# 05-SX1276.net
KiCad netlist of a schematic drawn in Altium Designer
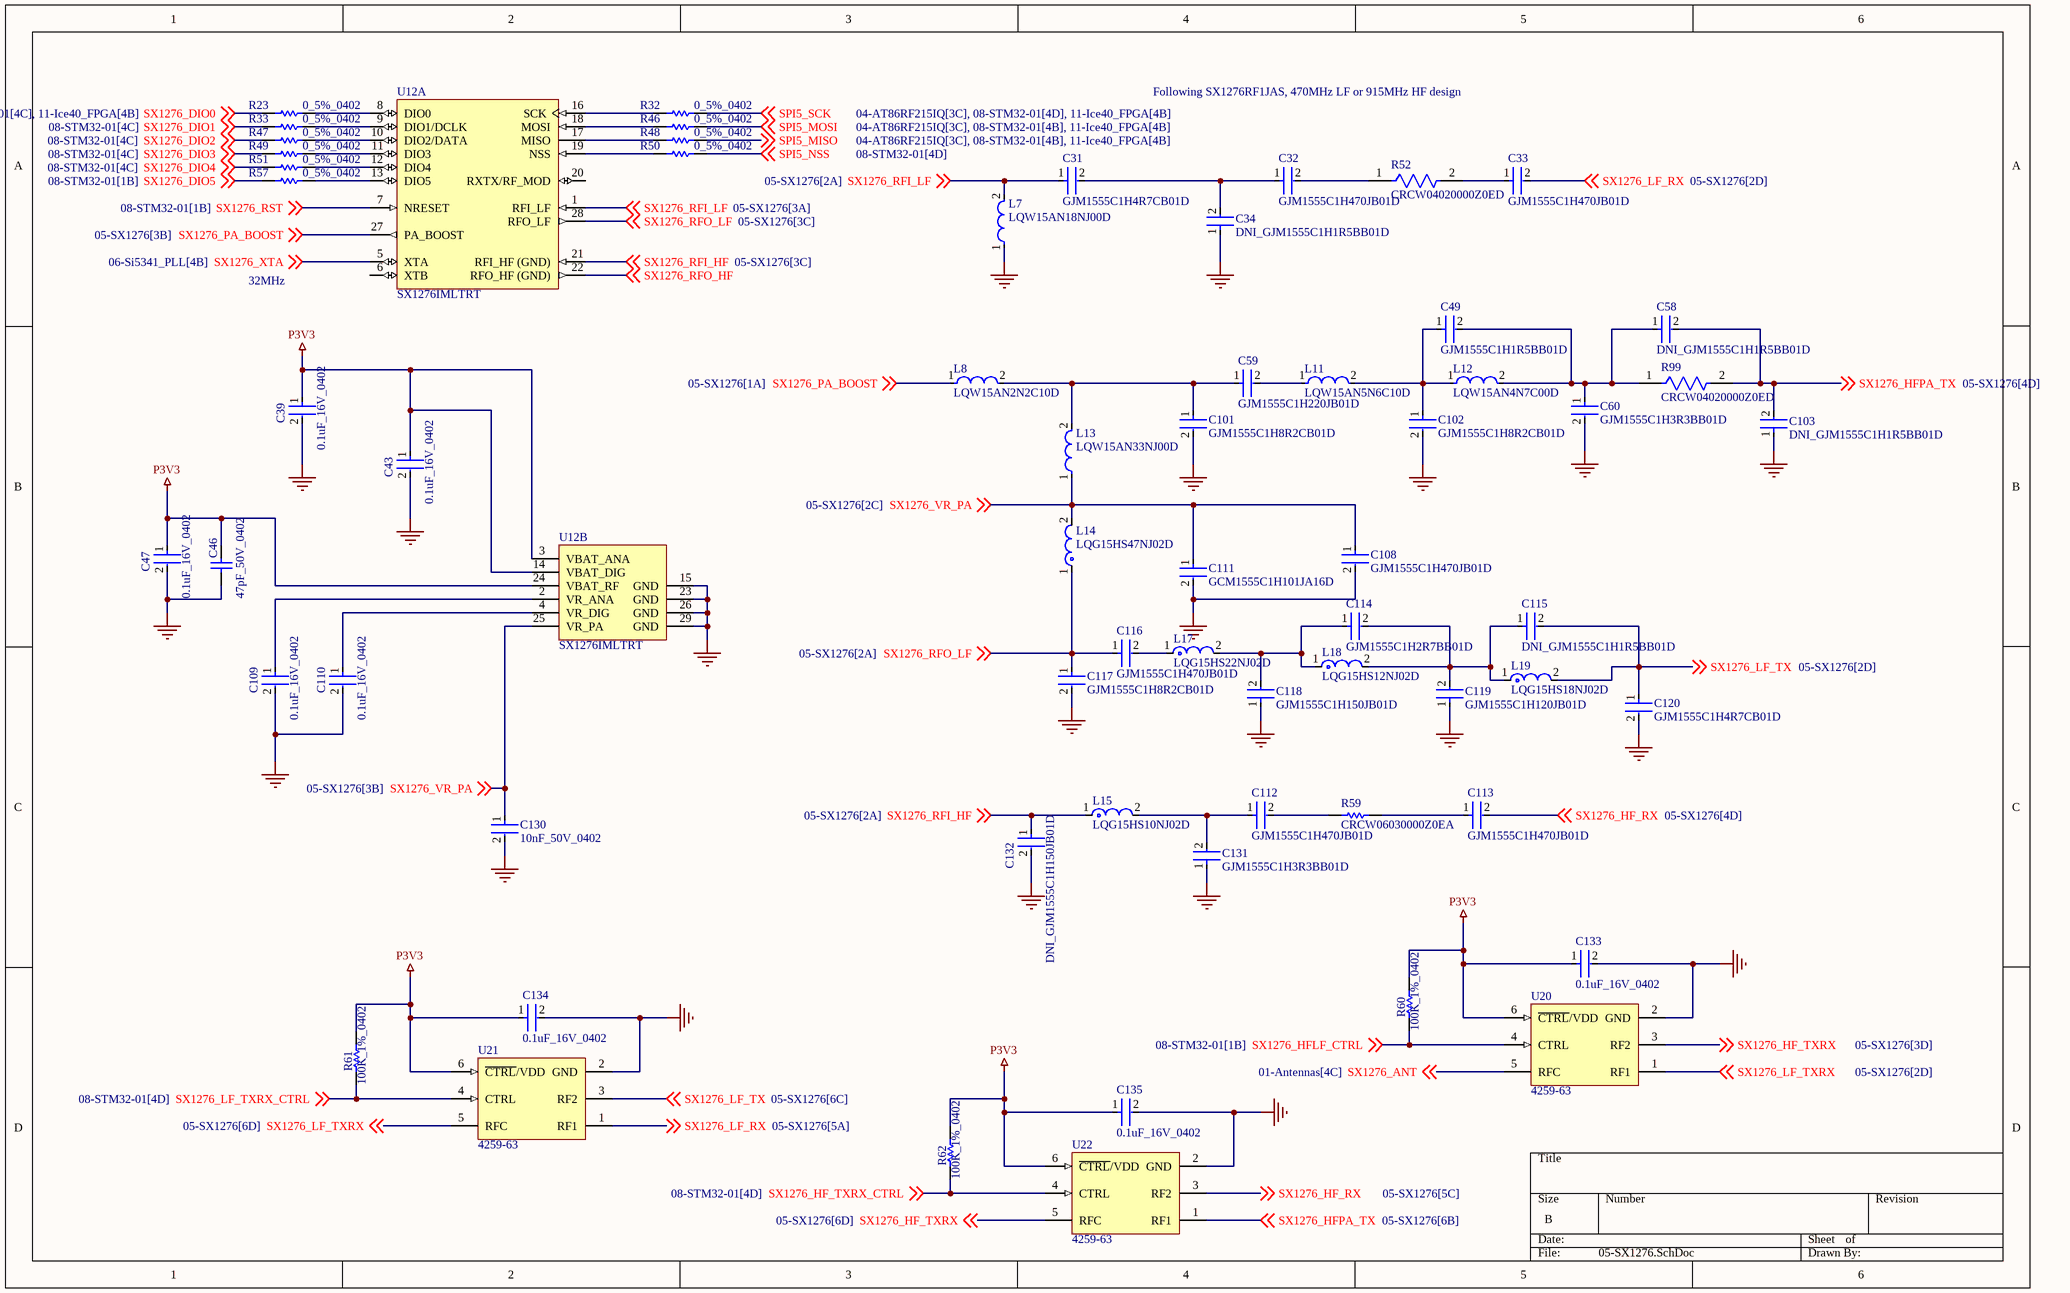
[diagram p0: 05-SX1276.SchDoc]

(export (version "E")
  (design (tool "Eeschema 10.0.6"))
  (components
    (comp (ref "C31")
      (value "GJM1555C1H4R7CB01D")
      (footprint "FP-GJM155-0_05-IPC_B")
      (description "Multi-Layer Ceramic Capacitor 4.7pF C0G  ±0.25pF 0402 Paper T/R")
      (fields (field (name "VOLTAGE") "50V"))
      (libsource (lib "Altium Content Vault") (part "02cd4be3c70576c341d710602a673aa"))
    )
    (comp (ref "C32")
      (value "GJM1555C1H470JB01D")
      (footprint "FP-GJM155-0_05-MFG")
      (description "Multi-Layer Ceramic Capacitor 47pF C0G  ±5% 0402 Paper T/R")
      (fields (field (name "TOLERANCE") "5%"))
      (libsource (lib "Altium Content Vault") (part "02cd4be3c70576c341d710602a673aa"))
    )
    (comp (ref "C33")
      (value "GJM1555C1H470JB01D")
      (footprint "FP-GJM155-0_05-MFG")
      (description "Multi-Layer Ceramic Capacitor 47pF C0G  ±5% 0402 Paper T/R")
      (fields (field (name "TOLERANCE") "5%"))
      (libsource (lib "Altium Content Vault") (part "02cd4be3c70576c341d710602a673aa"))
    )
    (comp (ref "C34")
      (value "DNI_GJM1555C1H1R5BB01D")
      (footprint "FP-GJM155-0_05-IPC_C")
      (description "Multi-Layer Ceramic Capacitor 1.5pF C0G  ±0.1pF 0402 Paper T/R")
      (fields (field (name "VOLTAGE") "50V"))
      (libsource (lib "Altium Content Vault") (part "02cd4be3c70576c341d710602a673aa"))
    )
    (comp (ref "C39")
      (value "0.1uF_16V_0402")
      (footprint "FP-C0402-BB-MFG")
      (description "CAP CER 0.1UF 16V 5% X7R 0402")
      (fields
        (field (name "MANUFACTURER") "Kemet")
        (field (name "MANUFACTURER PART NUMBER") "C0402C104J4RACTU")
      )
      (libsource (lib "Altium Content Vault") (part "b4654b650e69147ec39a6b967a45e02"))
    )
    (comp (ref "C43")
      (value "0.1uF_16V_0402")
      (footprint "FP-C0402-BB-MFG")
      (description "CAP CER 0.1UF 16V 5% X7R 0402")
      (fields
        (field (name "MANUFACTURER") "Kemet")
        (field (name "MANUFACTURER PART NUMBER") "C0402C104J4RACTU")
      )
      (libsource (lib "Altium Content Vault") (part "b4654b650e69147ec39a6b967a45e02"))
    )
    (comp (ref "C46")
      (value "47pF_50V_0402")
      (footprint "CAPC1005X55X25LL05T10")
      (fields (field (name "PART NUMBER") "GRM1555C1H470JA01D") (field (name "MANUFACTURER") "Murata"))
      (libsource (lib "Altium Content Vault") (part "CAP"))
    )
    (comp (ref "C47")
      (value "0.1uF_16V_0402")
      (footprint "FP-C0402-BB-MFG")
      (description "CAP CER 0.1UF 16V 5% X7R 0402")
      (fields
        (field (name "MANUFACTURER") "Kemet")
        (field (name "MANUFACTURER PART NUMBER") "C0402C104J4RACTU")
      )
      (libsource (lib "Altium Content Vault") (part "b4654b650e69147ec39a6b967a45e02"))
    )
    (comp (ref "C49")
      (value "GJM1555C1H1R5BB01D")
      (footprint "FP-GJM155-0_05-IPC_C")
      (description "Multi-Layer Ceramic Capacitor 1.5pF C0G  ±0.1pF 0402 Paper T/R")
      (fields (field (name "VOLTAGE") "50V"))
      (libsource (lib "Altium Content Vault") (part "02cd4be3c70576c341d710602a673aa"))
    )
    (comp (ref "C58")
      (value "DNI_GJM1555C1H1R5BB01D")
      (footprint "FP-GJM155-0_05-IPC_C")
      (description "Multi-Layer Ceramic Capacitor 1.5pF C0G  ±0.1pF 0402 Paper T/R")
      (fields (field (name "VOLTAGE") "50V"))
      (libsource (lib "Altium Content Vault") (part "02cd4be3c70576c341d710602a673aa"))
    )
    (comp (ref "C59")
      (value "GJM1555C1H220JB01D")
      (footprint "FP-GJM155-0_05-IPC_C")
      (description "Multi-Layer Ceramic Capacitor 22pF C0G  ±5% 0402 Paper T/R")
      (fields (field (name "TOLERANCE") "5%"))
      (libsource (lib "Altium Content Vault") (part "02cd4be3c70576c341d710602a673aa"))
    )
    (comp (ref "C60")
      (value "GJM1555C1H3R3BB01D")
      (footprint "FP-GJM155-0_05-IPC_C")
      (description "Multi-Layer Ceramic Capacitor 3.3pF C0G  ±0.1pF 0402 Paper T/R")
      (fields (field (name "VOLTAGE") "50V"))
      (libsource (lib "Altium Content Vault") (part "02cd4be3c70576c341d710602a673aa"))
    )
    (comp (ref "C101")
      (value "GJM1555C1H8R2CB01D")
      (footprint "FP-GJM155-0_05-IPC_C")
      (description "Multi-Layer Ceramic Capacitor 8.2pF C0G  ±0.25pF 0402 Paper T/R")
      (fields (field (name "VOLTAGE") "50V"))
      (libsource (lib "Altium Content Vault") (part "02cd4be3c70576c341d710602a673aa"))
    )
    (comp (ref "C102")
      (value "GJM1555C1H8R2CB01D")
      (footprint "FP-GJM155-0_05-IPC_C")
      (description "Multi-Layer Ceramic Capacitor 8.2pF C0G  ±0.25pF 0402 Paper T/R")
      (fields (field (name "VOLTAGE") "50V"))
      (libsource (lib "Altium Content Vault") (part "02cd4be3c70576c341d710602a673aa"))
    )
    (comp (ref "C103")
      (value "DNI_GJM1555C1H1R5BB01D")
      (footprint "FP-GJM155-0_05-IPC_C")
      (description "Multi-Layer Ceramic Capacitor 1.5pF C0G  ±0.1pF 0402 Paper T/R")
      (fields (field (name "VOLTAGE") "50V"))
      (libsource (lib "Altium Content Vault") (part "02cd4be3c70576c341d710602a673aa"))
    )
    (comp (ref "C108")
      (value "GJM1555C1H470JB01D")
      (footprint "FP-GJM155-0_05-MFG")
      (description "Multi-Layer Ceramic Capacitor 47pF C0G  ±5% 0402 Paper T/R")
      (fields (field (name "TOLERANCE") "5%"))
      (libsource (lib "Altium Content Vault") (part "02cd4be3c70576c341d710602a673aa"))
    )
    (comp (ref "C109")
      (value "0.1uF_16V_0402")
      (footprint "FP-C0402-BB-MFG")
      (description "CAP CER 0.1UF 16V 5% X7R 0402")
      (fields
        (field (name "MANUFACTURER") "Kemet")
        (field (name "MANUFACTURER PART NUMBER") "C0402C104J4RACTU")
      )
      (libsource (lib "Altium Content Vault") (part "b4654b650e69147ec39a6b967a45e02"))
    )
    (comp (ref "C110")
      (value "0.1uF_16V_0402")
      (footprint "FP-C0402-BB-MFG")
      (description "CAP CER 0.1UF 16V 5% X7R 0402")
      (fields
        (field (name "MANUFACTURER") "Kemet")
        (field (name "MANUFACTURER PART NUMBER") "C0402C104J4RACTU")
      )
      (libsource (lib "Altium Content Vault") (part "b4654b650e69147ec39a6b967a45e02"))
    )
    (comp (ref "C111")
      (value "GCM1555C1H101JA16D")
      (footprint "FP-GCM155-0_05-IPC_C")
      (description "Ceramic Capacitor for Automotive 100pF ±5% 50VDC C0G 0402 Paper T/R")
      (fields (field (name "VOLTAGE") "50V") (field (name "TOLERANCE") "5%"))
      (libsource (lib "Altium Content Vault") (part "02cd4be3c70576c341d710602a673aa"))
    )
    (comp (ref "C112")
      (value "GJM1555C1H470JB01D")
      (footprint "FP-GJM155-0_05-MFG")
      (description "Multi-Layer Ceramic Capacitor 47pF C0G  ±5% 0402 Paper T/R")
      (fields (field (name "TOLERANCE") "5%"))
      (libsource (lib "Altium Content Vault") (part "02cd4be3c70576c341d710602a673aa"))
    )
    (comp (ref "C113")
      (value "GJM1555C1H470JB01D")
      (footprint "FP-GJM155-0_05-MFG")
      (description "Multi-Layer Ceramic Capacitor 47pF C0G  ±5% 0402 Paper T/R")
      (fields (field (name "TOLERANCE") "5%"))
      (libsource (lib "Altium Content Vault") (part "02cd4be3c70576c341d710602a673aa"))
    )
    (comp (ref "C114")
      (value "GJM1555C1H2R7BB01D")
      (footprint "FP-GJM155-0_05-IPC_A")
      (description "Multi-Layer Ceramic Capacitor 2.7pF C0G  ±0.1pF 0402 Paper T/R")
      (fields (field (name "VOLTAGE") "50V"))
      (libsource (lib "Altium Content Vault") (part "02cd4be3c70576c341d710602a673aa"))
    )
    (comp (ref "C115")
      (value "DNI_GJM1555C1H1R5BB01D")
      (footprint "FP-GJM155-0_05-IPC_C")
      (description "Multi-Layer Ceramic Capacitor 1.5pF C0G  ±0.1pF 0402 Paper T/R")
      (fields (field (name "VOLTAGE") "50V"))
      (libsource (lib "Altium Content Vault") (part "02cd4be3c70576c341d710602a673aa"))
    )
    (comp (ref "C116")
      (value "GJM1555C1H470JB01D")
      (footprint "FP-GJM155-0_05-MFG")
      (description "Multi-Layer Ceramic Capacitor 47pF C0G  ±5% 0402 Paper T/R")
      (fields (field (name "TOLERANCE") "5%"))
      (libsource (lib "Altium Content Vault") (part "02cd4be3c70576c341d710602a673aa"))
    )
    (comp (ref "C117")
      (value "GJM1555C1H8R2CB01D")
      (footprint "FP-GJM155-0_05-IPC_C")
      (description "Multi-Layer Ceramic Capacitor 8.2pF C0G  ±0.25pF 0402 Paper T/R")
      (fields (field (name "VOLTAGE") "50V"))
      (libsource (lib "Altium Content Vault") (part "02cd4be3c70576c341d710602a673aa"))
    )
    (comp (ref "C118")
      (value "GJM1555C1H150JB01D")
      (footprint "FP-GJM155-0_05-IPC_A")
      (description "Multi-Layer Ceramic Capacitor 15pF C0G  ±5% 0402 Paper T/R")
      (fields (field (name "TOLERANCE") "5%") (field (name "VOLTAGE") "50V"))
      (libsource (lib "Altium Content Vault") (part "02cd4be3c70576c341d710602a673aa"))
    )
    (comp (ref "C119")
      (value "GJM1555C1H120JB01D")
      (footprint "FP-GJM155-0_05-IPC_A")
      (description "Multi-Layer Ceramic Capacitor 12pF C0G  ±5% 0402 Paper T/R")
      (fields (field (name "TOLERANCE") "5%") (field (name "VOLTAGE") "50V"))
      (libsource (lib "Altium Content Vault") (part "02cd4be3c70576c341d710602a673aa"))
    )
    (comp (ref "C120")
      (value "GJM1555C1H4R7CB01D")
      (footprint "FP-GJM155-0_05-IPC_B")
      (description "Multi-Layer Ceramic Capacitor 4.7pF C0G  ±0.25pF 0402 Paper T/R")
      (fields (field (name "VOLTAGE") "50V"))
      (libsource (lib "Altium Content Vault") (part "02cd4be3c70576c341d710602a673aa"))
    )
    (comp (ref "C130")
      (value "10nF_50V_0402")
      (footprint "FP-CL165-IPC_C")
      (description "Cap Ceramic 10nF 50V X7R ±10% SMD 0402 +125°C Paper T/R")
      (fields (field (name "VOLTAGE") "50V") (field (name "TOLERANCE") "10%"))
      (libsource (lib "Altium Content Vault") (part "b4654b650e69147ec39a6b967a45e02"))
    )
    (comp (ref "C131")
      (value "GJM1555C1H3R3BB01D")
      (footprint "FP-GJM155-0_05-IPC_C")
      (description "Multi-Layer Ceramic Capacitor 3.3pF C0G  ±0.1pF 0402 Paper T/R")
      (fields (field (name "VOLTAGE") "50V"))
      (libsource (lib "Altium Content Vault") (part "02cd4be3c70576c341d710602a673aa"))
    )
    (comp (ref "C132")
      (value "DNI_GJM1555C1H150JB01D")
      (footprint "FP-GJM155-0_05-IPC_A")
      (description "Multi-Layer Ceramic Capacitor 15pF C0G  ±5% 0402 Paper T/R")
      (fields (field (name "TOLERANCE") "5%") (field (name "VOLTAGE") "50V"))
      (libsource (lib "Altium Content Vault") (part "02cd4be3c70576c341d710602a673aa"))
    )
    (comp (ref "C133")
      (value "0.1uF_16V_0402")
      (footprint "FP-C0402-BB-MFG")
      (description "CAP CER 0.1UF 16V 5% X7R 0402")
      (fields
        (field (name "MANUFACTURER") "Kemet")
        (field (name "MANUFACTURER PART NUMBER") "C0402C104J4RACTU")
      )
      (libsource (lib "Altium Content Vault") (part "b4654b650e69147ec39a6b967a45e02"))
    )
    (comp (ref "C134")
      (value "0.1uF_16V_0402")
      (footprint "FP-C0402-BB-MFG")
      (description "CAP CER 0.1UF 16V 5% X7R 0402")
      (fields
        (field (name "MANUFACTURER") "Kemet")
        (field (name "MANUFACTURER PART NUMBER") "C0402C104J4RACTU")
      )
      (libsource (lib "Altium Content Vault") (part "b4654b650e69147ec39a6b967a45e02"))
    )
    (comp (ref "C135")
      (value "0.1uF_16V_0402")
      (footprint "FP-C0402-BB-MFG")
      (description "CAP CER 0.1UF 16V 5% X7R 0402")
      (fields
        (field (name "MANUFACTURER") "Kemet")
        (field (name "MANUFACTURER PART NUMBER") "C0402C104J4RACTU")
      )
      (libsource (lib "Altium Content Vault") (part "b4654b650e69147ec39a6b967a45e02"))
    )
    (comp (ref "L7")
      (value "LQW15AN18NJ00D")
      (footprint "FP-LQW15AN_00-W0_6-0_1-MFG")
      (description "Wire Wound RF Inductor 18nH ±5% 370mA 0.27Ω 0402 (1005)")
      (fields (field (name "TOLERANCE") "5%"))
      (libsource (lib "Altium Content Vault") (part "725321dda6339637d4d059423bc1c3c"))
    )
    (comp (ref "L8")
      (value "LQW15AN2N2C10D")
      (footprint "FP-LQW15AN_00-W0_6-0_1-MFG")
      (description "Wire Wound RF Inductor 2.2nH ±0.2nH 1000mA 0.027Ω 0402 (1005)")
      (libsource (lib "Altium Content Vault") (part "725321dda6339637d4d059423bc1c3c"))
    )
    (comp (ref "L11")
      (value "LQW15AN5N6C10D")
      (footprint "FP-LQW15AN_00-W0_6-0_1-MFG")
      (description "Wire Wound RF Inductor 5.6nH ±0.2nH 800mA 0.051Ω 0402 (1005)")
      (libsource (lib "Altium Content Vault") (part "725321dda6339637d4d059423bc1c3c"))
    )
    (comp (ref "L12")
      (value "LQW15AN4N7C00D")
      (footprint "FP-LQW15AN_00-W0_6-0_1-MFG")
      (description "Wire Wound RF Inductor 4.7nH ±0.2nH 750mA 0.07Ω 0402 (1005)")
      (libsource (lib "Altium Content Vault") (part "725321dda6339637d4d059423bc1c3c"))
    )
    (comp (ref "L13")
      (value "LQW15AN33NJ00D")
      (footprint "FP-LQW15AN_00-W0_5-0_1-MFG")
      (description "Wire Wound RF Inductor 33nH ±5% 260mA 0.63Ω 0402 (1005)")
      (fields (field (name "TOLERANCE") "5%"))
      (libsource (lib "Altium Content Vault") (part "725321dda6339637d4d059423bc1c3c"))
    )
    (comp (ref "L14")
      (value "LQG15HS47NJ02D")
      (footprint "FP-LQG15HH_02-IPC_B")
      (description "Multilayer type RF Inductor 47nH ±5% 0.72Ω 300mA 0402")
      (fields (field (name "TOLERANCE") "5%"))
      (libsource (lib "Altium Content Vault") (part "4cc4b267dca4c8e51f7102f422741d8"))
    )
    (comp (ref "L15")
      (value "LQG15HS10NJ02D")
      (footprint "FP-LQG15HH_02-IPC_A")
      (description "Multilayer type RF Inductor 10nH ±5% 0.26Ω 500mA 0402")
      (fields (field (name "TOLERANCE") "5%"))
      (libsource (lib "Altium Content Vault") (part "4cc4b267dca4c8e51f7102f422741d8"))
    )
    (comp (ref "L17")
      (value "LQG15HS22NJ02D")
      (footprint "FP-LQG15HH_02-MFG")
      (description "Multilayer type RF Inductor 22nH ±5% 0.42Ω 350mA 0402")
      (fields (field (name "TOLERANCE") "5%"))
      (libsource (lib "Altium Content Vault") (part "4cc4b267dca4c8e51f7102f422741d8"))
    )
    (comp (ref "L18")
      (value "LQG15HS12NJ02D")
      (footprint "FP-LQG15HH_02-IPC_A")
      (description "Multilayer type RF Inductor 12nH ±5% 0.28Ω 500mA 0402")
      (fields (field (name "TOLERANCE") "5%"))
      (libsource (lib "Altium Content Vault") (part "4cc4b267dca4c8e51f7102f422741d8"))
    )
    (comp (ref "L19")
      (value "LQG15HS18NJ02D")
      (footprint "FP-LQG15HH_02-MFG")
      (description "Multilayer type RF Inductor 18nH ±5% 0.36Ω 400mA 0402")
      (fields (field (name "TOLERANCE") "5%"))
      (libsource (lib "Altium Content Vault") (part "4cc4b267dca4c8e51f7102f422741d8"))
    )
    (comp (ref "R23")
      (value "0_5%_0402")
      (footprint "RESC1005X40X25NL05T10")
      (fields (field (name "MANUFACTURER") "Panasonic") (field (name "PART NUMBER") "ERJ-U020R00X"))
      (libsource (lib "Altium Content Vault") (part "RES"))
    )
    (comp (ref "R32")
      (value "0_5%_0402")
      (footprint "RESC1005X40X25NL05T10")
      (fields (field (name "MANUFACTURER") "Panasonic") (field (name "PART NUMBER") "ERJ-U020R00X"))
      (libsource (lib "Altium Content Vault") (part "RES"))
    )
    (comp (ref "R33")
      (value "0_5%_0402")
      (footprint "RESC1005X40X25NL05T10")
      (fields (field (name "MANUFACTURER") "Panasonic") (field (name "PART NUMBER") "ERJ-U020R00X"))
      (libsource (lib "Altium Content Vault") (part "RES"))
    )
    (comp (ref "R46")
      (value "0_5%_0402")
      (footprint "RESC1005X40X25NL05T10")
      (fields (field (name "MANUFACTURER") "Panasonic") (field (name "PART NUMBER") "ERJ-U020R00X"))
      (libsource (lib "Altium Content Vault") (part "RES"))
    )
    (comp (ref "R47")
      (value "0_5%_0402")
      (footprint "RESC1005X40X25NL05T10")
      (fields (field (name "MANUFACTURER") "Panasonic") (field (name "PART NUMBER") "ERJ-U020R00X"))
      (libsource (lib "Altium Content Vault") (part "RES"))
    )
    (comp (ref "R48")
      (value "0_5%_0402")
      (footprint "RESC1005X40X25NL05T10")
      (fields (field (name "MANUFACTURER") "Panasonic") (field (name "PART NUMBER") "ERJ-U020R00X"))
      (libsource (lib "Altium Content Vault") (part "RES"))
    )
    (comp (ref "R49")
      (value "0_5%_0402")
      (footprint "RESC1005X40X25NL05T10")
      (fields (field (name "MANUFACTURER") "Panasonic") (field (name "PART NUMBER") "ERJ-U020R00X"))
      (libsource (lib "Altium Content Vault") (part "RES"))
    )
    (comp (ref "R50")
      (value "0_5%_0402")
      (footprint "RESC1005X40X25NL05T10")
      (fields (field (name "MANUFACTURER") "Panasonic") (field (name "PART NUMBER") "ERJ-U020R00X"))
      (libsource (lib "Altium Content Vault") (part "RES"))
    )
    (comp (ref "R51")
      (value "0_5%_0402")
      (footprint "RESC1005X40X25NL05T10")
      (fields (field (name "MANUFACTURER") "Panasonic") (field (name "PART NUMBER") "ERJ-U020R00X"))
      (libsource (lib "Altium Content Vault") (part "RES"))
    )
    (comp (ref "R52")
      (value "CRCW04020000Z0ED")
      (footprint "FP-CRCW0402-e3-IPC_C")
      (description "RES Thick Film, 0Ω, 0.063W, 0402")
      (fields (field (name "TOLERANCE") "5%"))
      (libsource (lib "Altium Content Vault") (part "1029c3af85768c4190bb7ad29bc67b5"))
    )
    (comp (ref "R57")
      (value "0_5%_0402")
      (footprint "RESC1005X40X25NL05T10")
      (fields (field (name "MANUFACTURER") "Panasonic") (field (name "PART NUMBER") "ERJ-U020R00X"))
      (libsource (lib "Altium Content Vault") (part "RES"))
    )
    (comp (ref "R59")
      (value "CRCW06030000Z0EA")
      (footprint "RESC1609X50X30NL8T20")
      (description "Chip Resistor, 0 Ohm, Jumper, 100 mW, -55 to 155 degC, 0603 (1608 Metric), RoHS, Tape and Reel")
      (fields (field (name "MANUFACTURER") "Vishay Semiconductor"))
      (libsource (lib "Altium Content Vault") (part "RES-2"))
    )
    (comp (ref "R60")
      (value "100K_1%_0402")
      (footprint "RESC1005X40X25ML05T10")
      (fields (field (name "MANUFACTURER") "Yageo") (field (name "PART NUMBER") "RC0402FR-13100KL"))
      (libsource (lib "Altium Content Vault") (part "RES"))
    )
    (comp (ref "R61")
      (value "100K_1%_0402")
      (footprint "RESC1005X40X25ML05T10")
      (fields (field (name "MANUFACTURER") "Yageo") (field (name "PART NUMBER") "RC0402FR-13100KL"))
      (libsource (lib "Altium Content Vault") (part "RES"))
    )
    (comp (ref "R62")
      (value "100K_1%_0402")
      (footprint "RESC1005X40X25ML05T10")
      (fields (field (name "MANUFACTURER") "Yageo") (field (name "PART NUMBER") "RC0402FR-13100KL"))
      (libsource (lib "Altium Content Vault") (part "RES"))
    )
    (comp (ref "R99")
      (value "CRCW04020000Z0ED")
      (footprint "FP-CRCW0402-e3-IPC_C")
      (description "RES Thick Film, 0Ω, 0.063W, 0402")
      (fields (field (name "TOLERANCE") "5%"))
      (libsource (lib "Altium Content Vault") (part "1029c3af85768c4190bb7ad29bc67b5"))
    )
    (comp (ref "U12")
      (value "SX1276IMLTRT")
      (footprint "SMTC-QFN-28_V")
      (description "Low Power Long Range Transceiver, 137 to 1020 MHz, -40 to 85 degC, 28-Pin QFN, RoHS, Tape and Reel")
      (fields (field (name "MANUFACTURER") "Semtech"))
      (libsource (lib "Altium Content Vault") (part "SMTC-SX127X-QFN-28"))
    )
    (comp (ref "U20")
      (value "4259-63")
      (footprint "PERE-SC-70-6_M")
      (description "IC RF Switch SPDT, 50 Ohm, 6-Pin SC70, RoHS, Tape and Reel")
      (fields (field (name "MANUFACTURER") "Peregrine Semiconductor"))
      (libsource (lib "Altium Content Vault") (part "PERE-PE4259-6"))
    )
    (comp (ref "U21")
      (value "4259-63")
      (footprint "PERE-SC-70-6_M")
      (description "IC RF Switch SPDT, 50 Ohm, 6-Pin SC70, RoHS, Tape and Reel")
      (fields (field (name "MANUFACTURER") "Peregrine Semiconductor"))
      (libsource (lib "Altium Content Vault") (part "PERE-PE4259-6"))
    )
    (comp (ref "U22")
      (value "4259-63")
      (footprint "PERE-SC-70-6_M")
      (description "IC RF Switch SPDT, 50 Ohm, 6-Pin SC70, RoHS, Tape and Reel")
      (fields (field (name "MANUFACTURER") "Peregrine Semiconductor"))
      (libsource (lib "Altium Content Vault") (part "PERE-PE4259-6"))
    )
  )
  (nets
    (net (code "1") (name "GND") (class "Default")
      (node (ref "C101") (pin "2") (pinfunction "2_2") (pintype "passive"))
      (node (ref "C102") (pin "2") (pinfunction "2_2") (pintype "passive"))
      (node (ref "C103") (pin "1") (pinfunction "1_1") (pintype "passive"))
      (node (ref "C108") (pin "2") (pinfunction "2_2") (pintype "passive"))
      (node (ref "C109") (pin "2") (pinfunction "2_2") (pintype "passive"))
      (node (ref "C110") (pin "2") (pinfunction "2_2") (pintype "passive"))
      (node (ref "C111") (pin "2") (pinfunction "2_2") (pintype "passive"))
      (node (ref "C117") (pin "2") (pinfunction "2_2") (pintype "passive"))
      (node (ref "C118") (pin "1") (pinfunction "1_1") (pintype "passive"))
      (node (ref "C119") (pin "1") (pinfunction "1_1") (pintype "passive"))
      (node (ref "C120") (pin "2") (pinfunction "2_2") (pintype "passive"))
      (node (ref "C130") (pin "2") (pinfunction "2_2") (pintype "passive"))
      (node (ref "C131") (pin "1") (pinfunction "1_1") (pintype "passive"))
      (node (ref "C132") (pin "2") (pinfunction "2_2") (pintype "passive"))
      (node (ref "C133") (pin "2") (pinfunction "2_2") (pintype "passive"))
      (node (ref "C134") (pin "2") (pinfunction "2_2") (pintype "passive"))
      (node (ref "C135") (pin "2") (pinfunction "2_2") (pintype "passive"))
      (node (ref "C34") (pin "1") (pinfunction "1_1") (pintype "passive"))
      (node (ref "C39") (pin "2") (pinfunction "2_2") (pintype "passive"))
      (node (ref "C43") (pin "2") (pinfunction "2_2") (pintype "passive"))
      (node (ref "C46") (pin "1") (pinfunction "1_1") (pintype "passive"))
      (node (ref "C47") (pin "2") (pinfunction "2_2") (pintype "passive"))
      (node (ref "C60") (pin "2") (pinfunction "2_2") (pintype "passive"))
      (node (ref "L7") (pin "1") (pinfunction "1_1") (pintype "passive"))
      (node (ref "U12") (pin "15") (pinfunction "GND_15") (pintype "power_in"))
      (node (ref "U12") (pin "23") (pinfunction "GND_23") (pintype "power_in"))
      (node (ref "U12") (pin "26") (pinfunction "GND_26") (pintype "power_in"))
      (node (ref "U12") (pin "29") (pinfunction "GND_29") (pintype "power_in"))
      (node (ref "U20") (pin "2") (pinfunction "GND_2") (pintype "power_in"))
      (node (ref "U21") (pin "2") (pinfunction "GND_2") (pintype "power_in"))
      (node (ref "U22") (pin "2") (pinfunction "GND_2") (pintype "power_in"))
    )
    (net (code "2") (name "Net-(C31-Pad2)") (class "Default")
      (node (ref "C31") (pin "2") (pinfunction "2_2") (pintype "passive"))
      (node (ref "C32") (pin "1") (pinfunction "1_1") (pintype "passive"))
      (node (ref "C34") (pin "2") (pinfunction "2_2") (pintype "passive"))
    )
    (net (code "3") (name "Net-(C32-Pad2)") (class "Default")
      (node (ref "C32") (pin "2") (pinfunction "2_2") (pintype "passive"))
      (node (ref "R52") (pin "1") (pinfunction "1_1") (pintype "passive"))
    )
    (net (code "4") (name "Net-(C33-Pad1)") (class "Default")
      (node (ref "C33") (pin "1") (pinfunction "1_1") (pintype "passive"))
      (node (ref "R52") (pin "2") (pinfunction "2_2") (pintype "passive"))
    )
    (net (code "5") (name "Net-(C49-Pad2)") (class "Default")
      (node (ref "C49") (pin "2") (pinfunction "2_2") (pintype "passive"))
      (node (ref "C58") (pin "1") (pinfunction "1_1") (pintype "passive"))
      (node (ref "C60") (pin "1") (pinfunction "1_1") (pintype "passive"))
      (node (ref "L12") (pin "2") (pinfunction "2_2") (pintype "passive"))
      (node (ref "R99") (pin "1") (pinfunction "1_1") (pintype "passive"))
    )
    (net (code "6") (name "Net-(C59-Pad2)") (class "Default")
      (node (ref "C59") (pin "2") (pinfunction "2_2") (pintype "passive"))
      (node (ref "L11") (pin "1") (pinfunction "1_1") (pintype "passive"))
    )
    (net (code "7") (name "Net-(C101-Pad1)") (class "Default")
      (node (ref "C101") (pin "1") (pinfunction "1_1") (pintype "passive"))
      (node (ref "C59") (pin "1") (pinfunction "1_1") (pintype "passive"))
      (node (ref "L13") (pin "2") (pinfunction "2_2") (pintype "passive"))
      (node (ref "L8") (pin "2") (pinfunction "2_2") (pintype "passive"))
    )
    (net (code "8") (name "Net-(C102-Pad1)") (class "Default")
      (node (ref "C102") (pin "1") (pinfunction "1_1") (pintype "passive"))
      (node (ref "C49") (pin "1") (pinfunction "1_1") (pintype "passive"))
      (node (ref "L11") (pin "2") (pinfunction "2_2") (pintype "passive"))
      (node (ref "L12") (pin "1") (pinfunction "1_1") (pintype "passive"))
    )
    (net (code "9") (name "Net-(C112-Pad1)") (class "Default")
      (node (ref "C112") (pin "1") (pinfunction "1_1") (pintype "passive"))
      (node (ref "C131") (pin "2") (pinfunction "2_2") (pintype "passive"))
      (node (ref "L15") (pin "2") (pinfunction "2_2") (pintype "passive"))
    )
    (net (code "10") (name "Net-(C112-Pad2)") (class "Default")
      (node (ref "C112") (pin "2") (pinfunction "2_2") (pintype "passive"))
      (node (ref "R59") (pin "1") (pinfunction "1_1") (pintype "passive"))
    )
    (net (code "11") (name "Net-(C113-Pad1)") (class "Default")
      (node (ref "C113") (pin "1") (pinfunction "1_1") (pintype "passive"))
      (node (ref "R59") (pin "2") (pinfunction "2_2") (pintype "passive"))
    )
    (net (code "12") (name "Net-(C114-Pad1)") (class "Default")
      (node (ref "C114") (pin "1") (pinfunction "1_1") (pintype "passive"))
      (node (ref "C118") (pin "2") (pinfunction "2_2") (pintype "passive"))
      (node (ref "L17") (pin "2") (pinfunction "2_2") (pintype "passive"))
      (node (ref "L18") (pin "1") (pinfunction "1_1") (pintype "passive"))
    )
    (net (code "13") (name "Net-(C114-Pad2)") (class "Default")
      (node (ref "C114") (pin "2") (pinfunction "2_2") (pintype "passive"))
      (node (ref "C115") (pin "1") (pinfunction "1_1") (pintype "passive"))
      (node (ref "C119") (pin "2") (pinfunction "2_2") (pintype "passive"))
      (node (ref "L18") (pin "2") (pinfunction "2_2") (pintype "passive"))
      (node (ref "L19") (pin "1") (pinfunction "1_1") (pintype "passive"))
    )
    (net (code "14") (name "Net-(C116-Pad2)") (class "Default")
      (node (ref "C116") (pin "2") (pinfunction "2_2") (pintype "passive"))
      (node (ref "L17") (pin "1") (pinfunction "1_1") (pintype "passive"))
    )
    (net (code "15") (name "Net-(U12A-DIO0)") (class "Default")
      (node (ref "R23") (pin "2") (pinfunction "2_2") (pintype "passive"))
      (node (ref "U12") (pin "8") (pinfunction "DIO0_8") (pintype "bidirectional"))
    )
    (net (code "16") (name "Net-(U12A-DIO1{slash}DCLK)") (class "Default")
      (node (ref "R33") (pin "2") (pinfunction "2_2") (pintype "passive"))
      (node (ref "U12") (pin "9") (pinfunction "DIO1/DCLK_9") (pintype "bidirectional"))
    )
    (net (code "17") (name "Net-(U12A-DIO2{slash}DATA)") (class "Default")
      (node (ref "R47") (pin "2") (pinfunction "2_2") (pintype "passive"))
      (node (ref "U12") (pin "10") (pinfunction "DIO2/DATA_10") (pintype "bidirectional"))
    )
    (net (code "18") (name "Net-(U12A-DIO3)") (class "Default")
      (node (ref "R49") (pin "2") (pinfunction "2_2") (pintype "passive"))
      (node (ref "U12") (pin "11") (pinfunction "DIO3_11") (pintype "bidirectional"))
    )
    (net (code "19") (name "Net-(U12A-DIO4)") (class "Default")
      (node (ref "R51") (pin "2") (pinfunction "2_2") (pintype "passive"))
      (node (ref "U12") (pin "12") (pinfunction "DIO4_12") (pintype "bidirectional"))
    )
    (net (code "20") (name "Net-(U12A-DIO5)") (class "Default")
      (node (ref "R57") (pin "2") (pinfunction "2_2") (pintype "passive"))
      (node (ref "U12") (pin "13") (pinfunction "DIO5_13") (pintype "bidirectional"))
    )
    (net (code "21") (name "Net-(U12A-MISO)") (class "Default")
      (node (ref "R48") (pin "1") (pinfunction "1_1") (pintype "passive"))
      (node (ref "U12") (pin "17") (pinfunction "MISO_17") (pintype "tri_state"))
    )
    (net (code "22") (name "Net-(U12A-MOSI)") (class "Default")
      (node (ref "R46") (pin "1") (pinfunction "1_1") (pintype "passive"))
      (node (ref "U12") (pin "18") (pinfunction "MOSI_18") (pintype "input"))
    )
    (net (code "23") (name "Net-(U12A-NSS)") (class "Default")
      (node (ref "R50") (pin "1") (pinfunction "1_1") (pintype "passive"))
      (node (ref "U12") (pin "19") (pinfunction "NSS_19") (pintype "input"))
    )
    (net (code "24") (name "Net-(U12A-SCK)") (class "Default")
      (node (ref "R32") (pin "1") (pinfunction "1_1") (pintype "passive"))
      (node (ref "U12") (pin "16") (pinfunction "SCK_16") (pintype "input"))
    )
    (net (code "25") (name "Net-(U12B-VR_ANA)") (class "Default")
      (node (ref "C109") (pin "1") (pinfunction "1_1") (pintype "passive"))
      (node (ref "U12") (pin "2") (pinfunction "VR_ANA_2") (pintype "power_in"))
    )
    (net (code "26") (name "Net-(U12B-VR_DIG)") (class "Default")
      (node (ref "C110") (pin "1") (pinfunction "1_1") (pintype "passive"))
      (node (ref "U12") (pin "4") (pinfunction "VR_DIG_4") (pintype "power_in"))
    )
    (net (code "27") (name "P3V3") (class "Default")
      (node (ref "C133") (pin "1") (pinfunction "1_1") (pintype "passive"))
      (node (ref "C134") (pin "1") (pinfunction "1_1") (pintype "passive"))
      (node (ref "C135") (pin "1") (pinfunction "1_1") (pintype "passive"))
      (node (ref "C39") (pin "1") (pinfunction "1_1") (pintype "passive"))
      (node (ref "C43") (pin "1") (pinfunction "1_1") (pintype "passive"))
      (node (ref "C46") (pin "2") (pinfunction "2_2") (pintype "passive"))
      (node (ref "C47") (pin "1") (pinfunction "1_1") (pintype "passive"))
      (node (ref "R60") (pin "2") (pinfunction "2_2") (pintype "passive"))
      (node (ref "R61") (pin "2") (pinfunction "2_2") (pintype "passive"))
      (node (ref "R62") (pin "2") (pinfunction "2_2") (pintype "passive"))
      (node (ref "U12") (pin "14") (pinfunction "VBAT_DIG_14") (pintype "power_in"))
      (node (ref "U12") (pin "24") (pinfunction "VBAT_RF_24") (pintype "power_in"))
      (node (ref "U12") (pin "3") (pinfunction "VBAT_ANA_3") (pintype "power_in"))
      (node (ref "U20") (pin "6") (pinfunction "~{CTRL}/VDD_6") (pintype "input"))
      (node (ref "U21") (pin "6") (pinfunction "~{CTRL}/VDD_6") (pintype "input"))
      (node (ref "U22") (pin "6") (pinfunction "~{CTRL}/VDD_6") (pintype "input"))
    )
    (net (code "28") (name "SPI5_MISO") (class "Default")
      (node (ref "R48") (pin "2") (pinfunction "2_2") (pintype "passive"))
    )
    (net (code "29") (name "SPI5_MOSI") (class "Default")
      (node (ref "R46") (pin "2") (pinfunction "2_2") (pintype "passive"))
    )
    (net (code "30") (name "SPI5_NSS") (class "Default")
      (node (ref "R50") (pin "2") (pinfunction "2_2") (pintype "passive"))
    )
    (net (code "31") (name "SPI5_SCK") (class "Default")
      (node (ref "R32") (pin "2") (pinfunction "2_2") (pintype "passive"))
    )
    (net (code "32") (name "SX1276_ANT") (class "Default")
      (node (ref "U20") (pin "5") (pinfunction "RFC_5") (pintype "passive"))
    )
    (net (code "33") (name "SX1276_DIO0") (class "Default")
      (node (ref "R23") (pin "1") (pinfunction "1_1") (pintype "passive"))
    )
    (net (code "34") (name "SX1276_DIO1") (class "Default")
      (node (ref "R33") (pin "1") (pinfunction "1_1") (pintype "passive"))
    )
    (net (code "35") (name "SX1276_DIO2") (class "Default")
      (node (ref "R47") (pin "1") (pinfunction "1_1") (pintype "passive"))
    )
    (net (code "36") (name "SX1276_DIO3") (class "Default")
      (node (ref "R49") (pin "1") (pinfunction "1_1") (pintype "passive"))
    )
    (net (code "37") (name "SX1276_DIO4") (class "Default")
      (node (ref "R51") (pin "1") (pinfunction "1_1") (pintype "passive"))
    )
    (net (code "38") (name "SX1276_DIO5") (class "Default")
      (node (ref "R57") (pin "1") (pinfunction "1_1") (pintype "passive"))
    )
    (net (code "39") (name "SX1276_HFLF_CTRL") (class "Default")
      (node (ref "R60") (pin "1") (pinfunction "1_1") (pintype "passive"))
      (node (ref "U20") (pin "4") (pinfunction "CTRL_4") (pintype "input"))
    )
    (net (code "40") (name "SX1276_HFPA_TX") (class "Default")
      (node (ref "C103") (pin "2") (pinfunction "2_2") (pintype "passive"))
      (node (ref "C58") (pin "2") (pinfunction "2_2") (pintype "passive"))
      (node (ref "R99") (pin "2") (pinfunction "2_2") (pintype "passive"))
      (node (ref "U22") (pin "1") (pinfunction "RF1_1") (pintype "passive"))
    )
    (net (code "41") (name "SX1276_HF_RX") (class "Default")
      (node (ref "C113") (pin "2") (pinfunction "2_2") (pintype "passive"))
      (node (ref "U22") (pin "3") (pinfunction "RF2_3") (pintype "passive"))
    )
    (net (code "42") (name "SX1276_HF_TXRX") (class "Default")
      (node (ref "U20") (pin "3") (pinfunction "RF2_3") (pintype "passive"))
      (node (ref "U22") (pin "5") (pinfunction "RFC_5") (pintype "passive"))
    )
    (net (code "43") (name "SX1276_HF_TXRX_CTRL") (class "Default")
      (node (ref "R62") (pin "1") (pinfunction "1_1") (pintype "passive"))
      (node (ref "U22") (pin "4") (pinfunction "CTRL_4") (pintype "input"))
    )
    (net (code "44") (name "SX1276_LF_RX") (class "Default")
      (node (ref "C33") (pin "2") (pinfunction "2_2") (pintype "passive"))
      (node (ref "U21") (pin "1") (pinfunction "RF1_1") (pintype "passive"))
    )
    (net (code "45") (name "SX1276_LF_TX") (class "Default")
      (node (ref "C115") (pin "2") (pinfunction "2_2") (pintype "passive"))
      (node (ref "C120") (pin "1") (pinfunction "1_1") (pintype "passive"))
      (node (ref "L19") (pin "2") (pinfunction "2_2") (pintype "passive"))
      (node (ref "U21") (pin "3") (pinfunction "RF2_3") (pintype "passive"))
    )
    (net (code "46") (name "SX1276_LF_TXRX") (class "Default")
      (node (ref "U20") (pin "1") (pinfunction "RF1_1") (pintype "passive"))
      (node (ref "U21") (pin "5") (pinfunction "RFC_5") (pintype "passive"))
    )
    (net (code "47") (name "SX1276_LF_TXRX_CTRL") (class "Default")
      (node (ref "R61") (pin "1") (pinfunction "1_1") (pintype "passive"))
      (node (ref "U21") (pin "4") (pinfunction "CTRL_4") (pintype "input"))
    )
    (net (code "48") (name "SX1276_PA_BOOST") (class "Default")
      (node (ref "L8") (pin "1") (pinfunction "1_1") (pintype "passive"))
      (node (ref "U12") (pin "27") (pinfunction "PA_BOOST_27") (pintype "output"))
    )
    (net (code "49") (name "SX1276_RFI_HF") (class "Default")
      (node (ref "C132") (pin "1") (pinfunction "1_1") (pintype "passive"))
      (node (ref "L15") (pin "1") (pinfunction "1_1") (pintype "passive"))
      (node (ref "U12") (pin "21") (pinfunction "RFI_HF_(GND)_21") (pintype "input"))
    )
    (net (code "50") (name "SX1276_RFI_LF") (class "Default")
      (node (ref "C31") (pin "1") (pinfunction "1_1") (pintype "passive"))
      (node (ref "L7") (pin "2") (pinfunction "2_2") (pintype "passive"))
      (node (ref "U12") (pin "1") (pinfunction "RFI_LF_1") (pintype "input"))
    )
    (net (code "51") (name "SX1276_RFO_HF") (class "Default")
      (node (ref "U12") (pin "22") (pinfunction "RFO_HF_(GND)_22") (pintype "output"))
    )
    (net (code "52") (name "SX1276_RFO_LF") (class "Default")
      (node (ref "C116") (pin "1") (pinfunction "1_1") (pintype "passive"))
      (node (ref "C117") (pin "1") (pinfunction "1_1") (pintype "passive"))
      (node (ref "L14") (pin "1") (pinfunction "1_1") (pintype "passive"))
      (node (ref "U12") (pin "28") (pinfunction "RFO_LF_28") (pintype "output"))
    )
    (net (code "53") (name "SX1276_RST") (class "Default")
      (node (ref "U12") (pin "7") (pinfunction "NRESET_7") (pintype "input"))
    )
    (net (code "54") (name "SX1276_VR_PA") (class "Default")
      (node (ref "C108") (pin "1") (pinfunction "1_1") (pintype "passive"))
      (node (ref "C111") (pin "1") (pinfunction "1_1") (pintype "passive"))
      (node (ref "C130") (pin "1") (pinfunction "1_1") (pintype "passive"))
      (node (ref "L13") (pin "1") (pinfunction "1_1") (pintype "passive"))
      (node (ref "L14") (pin "2") (pinfunction "2_2") (pintype "passive"))
      (node (ref "U12") (pin "25") (pinfunction "VR_PA_25") (pintype "power_in"))
    )
    (net (code "55") (name "SX1276_XTA") (class "Default")
      (node (ref "U12") (pin "5") (pinfunction "XTA_5") (pintype "bidirectional"))
    )
    (net (code "56") (name "unconnected-(U12A-RXTX{slash}RF_MOD-Pad20)") (class "Default")
      (node (ref "U12") (pin "20") (pinfunction "RXTX/RF_MOD_20") (pintype "bidirectional"))
    )
    (net (code "57") (name "unconnected-(U12A-XTB-Pad6)") (class "Default")
      (node (ref "U12") (pin "6") (pinfunction "XTB_6") (pintype "bidirectional"))
    )
  )
)
